# Sheet1.net
KiCad netlist of a schematic drawn in Altium Designer
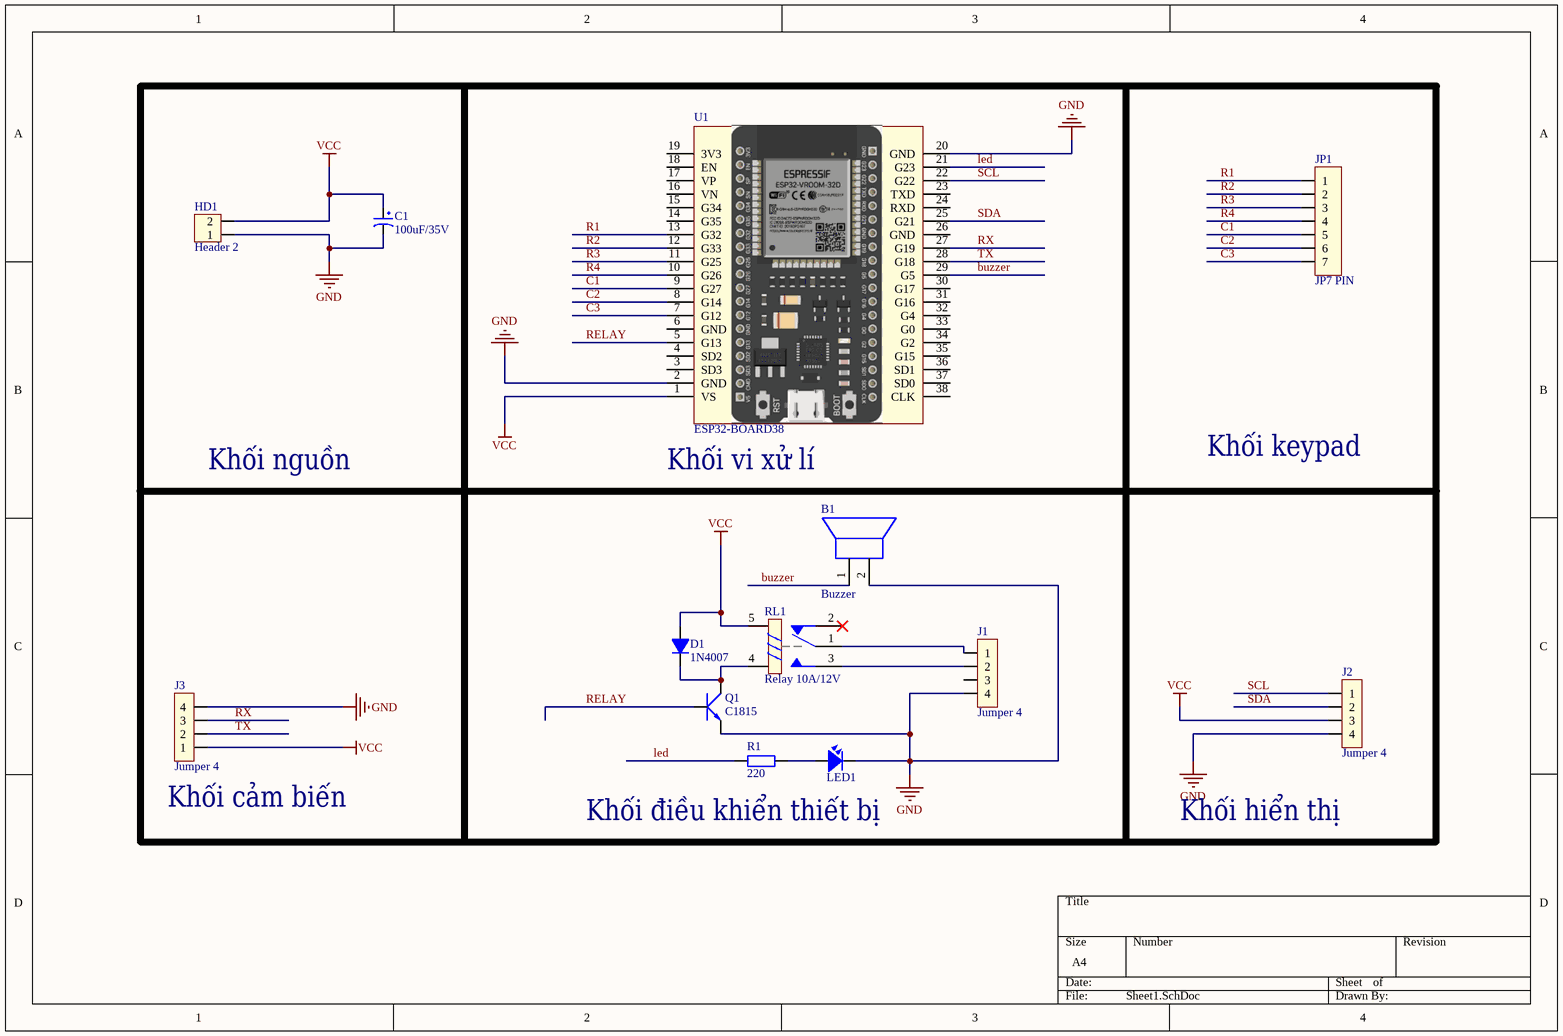
[diagram p0: Sheet1.SchDoc]

(export (version "E")
  (design (tool "Eeschema 10.0.6"))
  (components
    (comp (ref "B1")
      (value "Buzzer")
      (footprint "MinhTien_PcbLib:Buzzer")
      (libsource (lib "MinhTien_SCHLib") (part "Buzzer"))
    )
    (comp (ref "C1")
      (value "100uF/35V")
      (footprint "CP1.5/3.4")
      (description "Cap 100uF/35V - 470uF/16V")
      (libsource (lib "Thuvien3D") (part "CP3"))
    )
    (comp (ref "D1")
      (value "1N4007")
      (footprint "D1A")
      (description "Diode 1A")
      (libsource (lib "Thuvien3D") (part "D1A"))
    )
    (comp (ref "HD1")
      (value "Header 2")
      (footprint "PART:HED2")
      (description "Header 2 (Green)")
      (libsource (lib "PART") (part "Hed2"))
    )
    (comp (ref "J1") (value "Jumper 4") (footprint "PART:JP4") (libsource (lib "PART") (part "JP4")))
    (comp (ref "J2") (value "Jumper 4") (footprint "PART:JP4") (libsource (lib "PART") (part "JP4")))
    (comp (ref "J3") (value "Jumper 4") (footprint "PART:JP4") (libsource (lib "") (part "JP4_1")))
    (comp (ref "JP1") (value "JP7 PIN") (footprint "Part:JP7") (libsource (lib "PART") (part "JP7")))
    (comp (ref "LED1")
      (value "LED")
      (footprint "LED-3")
      (description "LED Single colour Green and Red")
      (libsource (lib "Thuvien3D") (part "LED"))
    )
    (comp (ref "Q1")
      (value "C1815")
      (footprint "QTO-92")
      (description "NPN 600mW, ECB")
      (libsource (lib "PART") (part "C1815"))
    )
    (comp (ref "R1")
      (value "220")
      (footprint "R1/4W")
      (description "Resistor 1/4W")
      (libsource (lib "Thuvien3D") (part "R1/4W"))
    )
    (comp (ref "RL1")
      (value "Relay 10A/12V")
      (footprint "RL_SPDT_10A")
      (description "Relay SPDT,10A - 12VDC 5 Pin")
      (libsource (lib "Thuvien3D") (part "Relay 1"))
    )
    (comp (ref "U1")
      (value "ESP32-BOARD38")
      (footprint "ESP32-BOARD38-900")
      (libsource (lib "PART") (part "ESP32-BOARD38"))
    )
  )
  (nets
    (net (code "1") (name "/C1") (class "Default")
      (node (ref "JP1") (pin "5") (pinfunction "5_5") (pintype "passive"))
      (node (ref "U1") (pin "9") (pinfunction "G27_9") (pintype "passive"))
    )
    (net (code "2") (name "/C2") (class "Default")
      (node (ref "JP1") (pin "6") (pinfunction "6_6") (pintype "passive"))
      (node (ref "U1") (pin "8") (pinfunction "G14_8") (pintype "passive"))
    )
    (net (code "3") (name "/C3") (class "Default")
      (node (ref "JP1") (pin "7") (pinfunction "7_7") (pintype "passive"))
      (node (ref "U1") (pin "7") (pinfunction "G12_7") (pintype "passive"))
    )
    (net (code "4") (name "/R1") (class "Default")
      (node (ref "JP1") (pin "1") (pinfunction "1_1") (pintype "passive"))
      (node (ref "U1") (pin "13") (pinfunction "G32_13") (pintype "passive"))
    )
    (net (code "5") (name "/R2") (class "Default")
      (node (ref "JP1") (pin "2") (pinfunction "2_2") (pintype "passive"))
      (node (ref "U1") (pin "12") (pinfunction "G33_12") (pintype "passive"))
    )
    (net (code "6") (name "/R3") (class "Default")
      (node (ref "JP1") (pin "3") (pinfunction "3_3") (pintype "passive"))
      (node (ref "U1") (pin "11") (pinfunction "G25_11") (pintype "passive"))
    )
    (net (code "7") (name "/R4") (class "Default")
      (node (ref "JP1") (pin "4") (pinfunction "4_4") (pintype "passive"))
      (node (ref "U1") (pin "10") (pinfunction "G26_10") (pintype "passive"))
    )
    (net (code "8") (name "/RELAY") (class "Default")
      (node (ref "Q1") (pin "3") (pinfunction "B_3") (pintype "passive"))
      (node (ref "U1") (pin "5") (pinfunction "G13_5") (pintype "passive"))
    )
    (net (code "9") (name "/RX") (class "Default")
      (node (ref "J3") (pin "3") (pinfunction "3_3") (pintype "passive"))
      (node (ref "U1") (pin "27") (pinfunction "G19_27") (pintype "passive"))
    )
    (net (code "10") (name "/SCL") (class "Default")
      (node (ref "J2") (pin "1") (pinfunction "1_1") (pintype "passive"))
      (node (ref "U1") (pin "22") (pinfunction "G22_22") (pintype "passive"))
    )
    (net (code "11") (name "/SDA") (class "Default")
      (node (ref "J2") (pin "2") (pinfunction "2_2") (pintype "passive"))
      (node (ref "U1") (pin "25") (pinfunction "G21_25") (pintype "passive"))
    )
    (net (code "12") (name "/TX") (class "Default")
      (node (ref "J3") (pin "2") (pinfunction "2_2") (pintype "passive"))
      (node (ref "U1") (pin "28") (pinfunction "G18_28") (pintype "passive"))
    )
    (net (code "13") (name "/buzzer") (class "Default")
      (node (ref "B1") (pin "1") (pinfunction "+_1") (pintype "passive"))
      (node (ref "U1") (pin "29") (pinfunction "G5_29") (pintype "passive"))
    )
    (net (code "14") (name "/led") (class "Default")
      (node (ref "R1") (pin "1") (pinfunction "1_1") (pintype "passive"))
      (node (ref "U1") (pin "21") (pinfunction "G23_21") (pintype "passive"))
    )
    (net (code "15") (name "GND") (class "Default")
      (node (ref "B1") (pin "2") (pinfunction "-_2") (pintype "passive"))
      (node (ref "C1") (pin "2") (pinfunction "2_2") (pintype "passive"))
      (node (ref "HD1") (pin "1") (pinfunction "1_1") (pintype "passive"))
      (node (ref "J1") (pin "4") (pinfunction "4_4") (pintype "passive"))
      (node (ref "J2") (pin "4") (pinfunction "4_4") (pintype "passive"))
      (node (ref "J3") (pin "4") (pinfunction "4_4") (pintype "passive"))
      (node (ref "LED1") (pin "2") (pinfunction "2_2") (pintype "passive"))
      (node (ref "Q1") (pin "1") (pinfunction "E_1") (pintype "passive"))
      (node (ref "U1") (pin "2") (pinfunction "GND_2") (pintype "passive"))
      (node (ref "U1") (pin "20") (pinfunction "GND_20") (pintype "passive"))
    )
    (net (code "16") (name "Net-(D1-K)") (class "Default")
      (node (ref "D1") (pin "2") (pinfunction "K_2") (pintype "passive"))
      (node (ref "Q1") (pin "2") (pinfunction "C_2") (pintype "passive"))
      (node (ref "RL1") (pin "4") (pinfunction "4_4") (pintype "passive"))
    )
    (net (code "17") (name "Net-(J1-Pad1)") (class "Default")
      (node (ref "J1") (pin "1") (pinfunction "1_1") (pintype "passive"))
      (node (ref "RL1") (pin "1") (pinfunction "1_1") (pintype "passive"))
    )
    (net (code "18") (name "Net-(J1-Pad2)") (class "Default")
      (node (ref "J1") (pin "2") (pinfunction "2_2") (pintype "passive"))
      (node (ref "RL1") (pin "3") (pinfunction "3_3") (pintype "passive"))
    )
    (net (code "19") (name "Net-(LED1-Pad1)") (class "Default")
      (node (ref "LED1") (pin "1") (pinfunction "1_1") (pintype "passive"))
      (node (ref "R1") (pin "2") (pinfunction "2_2") (pintype "passive"))
    )
    (net (code "20") (name "VCC") (class "Default")
      (node (ref "C1") (pin "1") (pinfunction "1_1") (pintype "passive"))
      (node (ref "D1") (pin "1") (pinfunction "A_1") (pintype "passive"))
      (node (ref "HD1") (pin "2") (pinfunction "2_2") (pintype "passive"))
      (node (ref "J2") (pin "3") (pinfunction "3_3") (pintype "passive"))
      (node (ref "J3") (pin "1") (pinfunction "1_1") (pintype "passive"))
      (node (ref "RL1") (pin "5") (pinfunction "5_5") (pintype "passive"))
      (node (ref "U1") (pin "1") (pinfunction "VS_1") (pintype "passive"))
    )
    (net (code "21") (name "unconnected-(J1-Pad3)") (class "Default")
      (node (ref "J1") (pin "3") (pinfunction "3_3") (pintype "passive"))
    )
    (net (code "22") (name "unconnected-(RL1-Pad2)") (class "Default")
      (node (ref "RL1") (pin "2") (pinfunction "2_2") (pintype "passive+no_connect"))
    )
    (net (code "23") (name "unconnected-(U1-3V3-Pad19)") (class "Default")
      (node (ref "U1") (pin "19") (pinfunction "3V3_19") (pintype "passive"))
    )
    (net (code "24") (name "unconnected-(U1-CLK-Pad38)") (class "Default")
      (node (ref "U1") (pin "38") (pinfunction "CLK_38") (pintype "passive"))
    )
    (net (code "25") (name "unconnected-(U1-EN-Pad18)") (class "Default")
      (node (ref "U1") (pin "18") (pinfunction "EN_18") (pintype "passive"))
    )
    (net (code "26") (name "unconnected-(U1-G0-Pad33)") (class "Default")
      (node (ref "U1") (pin "33") (pinfunction "G0_33") (pintype "passive"))
    )
    (net (code "27") (name "unconnected-(U1-G2-Pad34)") (class "Default")
      (node (ref "U1") (pin "34") (pinfunction "G2_34") (pintype "passive"))
    )
    (net (code "28") (name "unconnected-(U1-G4-Pad32)") (class "Default")
      (node (ref "U1") (pin "32") (pinfunction "G4_32") (pintype "passive"))
    )
    (net (code "29") (name "unconnected-(U1-G15-Pad35)") (class "Default")
      (node (ref "U1") (pin "35") (pinfunction "G15_35") (pintype "passive"))
    )
    (net (code "30") (name "unconnected-(U1-G16-Pad31)") (class "Default")
      (node (ref "U1") (pin "31") (pinfunction "G16_31") (pintype "passive"))
    )
    (net (code "31") (name "unconnected-(U1-G17-Pad30)") (class "Default")
      (node (ref "U1") (pin "30") (pinfunction "G17_30") (pintype "passive"))
    )
    (net (code "32") (name "unconnected-(U1-G34-Pad15)") (class "Default")
      (node (ref "U1") (pin "15") (pinfunction "G34_15") (pintype "passive"))
    )
    (net (code "33") (name "unconnected-(U1-G35-Pad14)") (class "Default")
      (node (ref "U1") (pin "14") (pinfunction "G35_14") (pintype "passive"))
    )
    (net (code "34") (name "unconnected-(U1-GND-Pad6)") (class "Default")
      (node (ref "U1") (pin "6") (pinfunction "GND_6") (pintype "passive"))
    )
    (net (code "35") (name "unconnected-(U1-GND-Pad26)") (class "Default")
      (node (ref "U1") (pin "26") (pinfunction "GND_26") (pintype "passive"))
    )
    (net (code "36") (name "unconnected-(U1-RXD-Pad24)") (class "Default")
      (node (ref "U1") (pin "24") (pinfunction "RXD_24") (pintype "passive"))
    )
    (net (code "37") (name "unconnected-(U1-SD0-Pad37)") (class "Default")
      (node (ref "U1") (pin "37") (pinfunction "SD0_37") (pintype "passive"))
    )
    (net (code "38") (name "unconnected-(U1-SD1-Pad36)") (class "Default")
      (node (ref "U1") (pin "36") (pinfunction "SD1_36") (pintype "passive"))
    )
    (net (code "39") (name "unconnected-(U1-SD2-Pad4)") (class "Default")
      (node (ref "U1") (pin "4") (pinfunction "SD2_4") (pintype "passive"))
    )
    (net (code "40") (name "unconnected-(U1-SD3-Pad3)") (class "Default")
      (node (ref "U1") (pin "3") (pinfunction "SD3_3") (pintype "passive"))
    )
    (net (code "41") (name "unconnected-(U1-TXD-Pad23)") (class "Default")
      (node (ref "U1") (pin "23") (pinfunction "TXD_23") (pintype "passive"))
    )
    (net (code "42") (name "unconnected-(U1-VN-Pad16)") (class "Default")
      (node (ref "U1") (pin "16") (pinfunction "VN_16") (pintype "passive"))
    )
    (net (code "43") (name "unconnected-(U1-VP-Pad17)") (class "Default")
      (node (ref "U1") (pin "17") (pinfunction "VP_17") (pintype "passive"))
    )
  )
)
